# SEM002_2003_-_FanControl.net
KiCad netlist of a schematic drawn in EAGLE
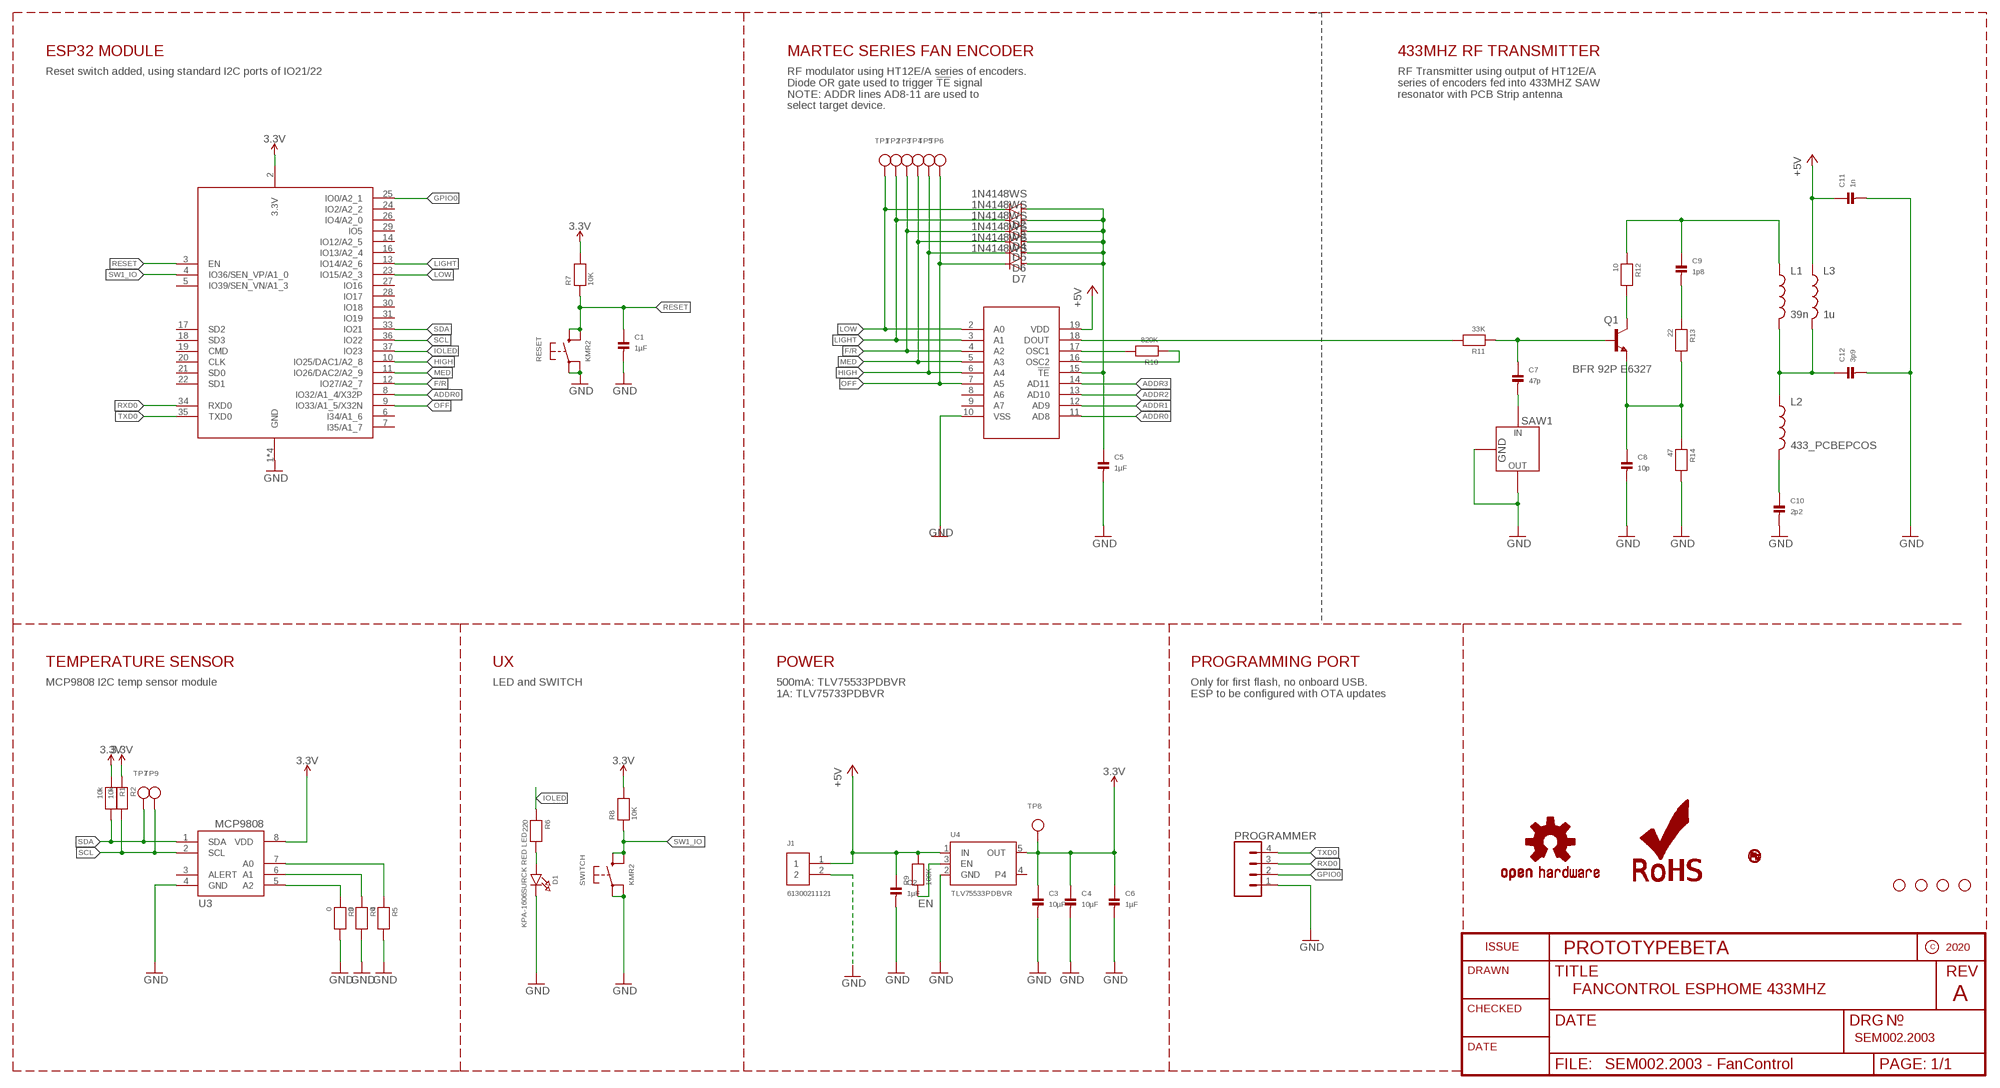
[diagram p0: schematic, sheet 1]

(export (version "E")
  (design (tool "Eeschema 10.0.6"))
  (components
    (comp (ref "C1")
      (value "1µF")
      (footprint "eagle-import:0603")
      (fields (field (name "MPN") "LMK107B7105KA-T"))
      (libsource (lib "eagle-import") (part "CAP_CERAMIC0603"))
    )
    (comp (ref "C2")
      (value "1µF")
      (footprint "eagle-import:0805_NOTHERMALS")
      (fields (field (name "MPN") "LMK107B7105KA-T"))
      (libsource (lib "eagle-import") (part "CAP_CERAMIC0805-NOTHERMALS"))
    )
    (comp (ref "C3")
      (value "10µF")
      (footprint "eagle-import:0603")
      (fields (field (name "MPN") "0805YD106MAT4A"))
      (libsource (lib "eagle-import") (part "CAP_CERAMIC0603"))
    )
    (comp (ref "C4")
      (value "10µF")
      (footprint "eagle-import:0805_NOTHERMALS")
      (fields (field (name "MPN") "0805YD106MAT4A"))
      (libsource (lib "eagle-import") (part "CAP_CERAMIC0805-NOTHERMALS"))
    )
    (comp (ref "C5")
      (value "1µF")
      (footprint "eagle-import:0603-MINI")
      (fields (field (name "MPN") "LMK107B7105KA-T"))
      (libsource (lib "eagle-import") (part "CAP_CERAMIC0603MINI"))
    )
    (comp (ref "C6")
      (value "1µF")
      (footprint "eagle-import:0603")
      (fields (field (name "MPN") "LMK107B7105KA-T"))
      (libsource (lib "eagle-import") (part "CAP_CERAMIC0603"))
    )
    (comp (ref "C7")
      (value "47p")
      (footprint "eagle-import:0603-MINI")
      (fields (field (name "MPN") "0603N470F500CT"))
      (libsource (lib "eagle-import") (part "CAP_CERAMIC0603MINI"))
    )
    (comp (ref "C8")
      (value "10p")
      (footprint "eagle-import:0603-MINI")
      (fields (field (name "MPN") "0603N100F500CT"))
      (libsource (lib "eagle-import") (part "CAP_CERAMIC0603MINI"))
    )
    (comp (ref "C9")
      (value "1p8")
      (footprint "eagle-import:0603-MINI")
      (fields (field (name "MPN") "0603N1R8B101CT"))
      (libsource (lib "eagle-import") (part "CAP_CERAMIC0603MINI"))
    )
    (comp (ref "C10")
      (value "2p2")
      (footprint "eagle-import:0603-MINI")
      (fields (field (name "MPN") "0603N2R2B101CT"))
      (libsource (lib "eagle-import") (part "CAP_CERAMIC0603MINI"))
    )
    (comp (ref "C11")
      (value "1n")
      (footprint "eagle-import:0603-MINI")
      (fields (field (name "MPN") "0603N102F500CT"))
      (libsource (lib "eagle-import") (part "CAP_CERAMIC0603MINI"))
    )
    (comp (ref "C12")
      (value "3p9")
      (footprint "eagle-import:0603-MINI")
      (fields (field (name "MPN") "0603N3R9B101CT"))
      (libsource (lib "eagle-import") (part "CAP_CERAMIC0603MINI"))
    )
    (comp (ref "D1")
      (value "KPA-1606SURCK RED LED")
      (footprint "eagle-import:CHIPLED_0603")
      (fields (field (name "MPN") "SML-H12U8TT86C"))
      (libsource (lib "eagle-import") (part "LED0603"))
    )
    (comp (ref "D2")
      (value "1N4148WS")
      (footprint "eagle-import:SOD-323")
      (fields
        (field (name "DIGIKEY_PART_NUMBER") "1N4148WSFSTR-ND")
        (field (name "MANUFACTURER") "Diodes Incorporated")
        (field (name "CREATED_BY") "PCBLayout.com")
      )
      (libsource (lib "eagle-import") (part "1N4148WS"))
    )
    (comp (ref "D3")
      (value "1N4148WS")
      (footprint "eagle-import:SOD-323")
      (fields
        (field (name "DIGIKEY_PART_NUMBER") "1N4148WSFSTR-ND")
        (field (name "MANUFACTURER") "Diodes Incorporated")
        (field (name "CREATED_BY") "PCBLayout.com")
      )
      (libsource (lib "eagle-import") (part "1N4148WS"))
    )
    (comp (ref "D4")
      (value "1N4148WS")
      (footprint "eagle-import:SOD-323")
      (fields
        (field (name "DIGIKEY_PART_NUMBER") "1N4148WSFSTR-ND")
        (field (name "MANUFACTURER") "Diodes Incorporated")
        (field (name "CREATED_BY") "PCBLayout.com")
      )
      (libsource (lib "eagle-import") (part "1N4148WS"))
    )
    (comp (ref "D5")
      (value "1N4148WS")
      (footprint "eagle-import:SOD-323")
      (fields
        (field (name "DIGIKEY_PART_NUMBER") "1N4148WSFSTR-ND")
        (field (name "MANUFACTURER") "Diodes Incorporated")
        (field (name "CREATED_BY") "PCBLayout.com")
      )
      (libsource (lib "eagle-import") (part "1N4148WS"))
    )
    (comp (ref "D6")
      (value "1N4148WS")
      (footprint "eagle-import:SOD-323")
      (fields
        (field (name "DIGIKEY_PART_NUMBER") "1N4148WSFSTR-ND")
        (field (name "MANUFACTURER") "Diodes Incorporated")
        (field (name "CREATED_BY") "PCBLayout.com")
      )
      (libsource (lib "eagle-import") (part "1N4148WS"))
    )
    (comp (ref "D7")
      (value "1N4148WS")
      (footprint "eagle-import:SOD-323")
      (fields
        (field (name "DIGIKEY_PART_NUMBER") "1N4148WSFSTR-ND")
        (field (name "MANUFACTURER") "Diodes Incorporated")
        (field (name "CREATED_BY") "PCBLayout.com")
      )
      (libsource (lib "eagle-import") (part "1N4148WS"))
    )
    (comp (ref "H1")
      (value "STAND-OFF")
      (footprint "eagle-import:STAND-OFF")
      (libsource (lib "eagle-import") (part "STAND-OFF"))
    )
    (comp (ref "H2")
      (value "STAND-OFF")
      (footprint "eagle-import:STAND-OFF")
      (libsource (lib "eagle-import") (part "STAND-OFF"))
    )
    (comp (ref "H3")
      (value "STAND-OFF")
      (footprint "eagle-import:STAND-OFF")
      (libsource (lib "eagle-import") (part "STAND-OFF"))
    )
    (comp (ref "H4")
      (value "STAND-OFF")
      (footprint "eagle-import:STAND-OFF")
      (libsource (lib "eagle-import") (part "STAND-OFF"))
    )
    (comp (ref "J1")
      (value "61300211121")
      (footprint "eagle-import:61300211121")
      (fields
        (field (name "DIGI_KEY_PART_NUMBER") "732-5315-ND")
        (field (name "MANUFACTURER") "Wurth Electronics Inc.")
        (field (name "CREATED_BY") "PCBLayout.com")
      )
      (libsource (lib "eagle-import") (part "61300211121"))
    )
    (comp (ref "L1")
      (value "39n")
      (footprint "eagle-import:L0603")
      (fields (field (name "MPN") "CI160808-39NJ"))
      (libsource (lib "eagle-import") (part "INDUCTOR"))
    )
    (comp (ref "L2")
      (value "433_PCBEPCOS")
      (footprint "eagle-import:433MHZ-SAW")
      (libsource (lib "eagle-import") (part "433_PCBEPCOS"))
    )
    (comp (ref "L3")
      (value "1u")
      (footprint "eagle-import:L0603")
      (fields (field (name "MPN") "AIML-0603-1R0K-T"))
      (libsource (lib "eagle-import") (part "INDUCTOR"))
    )
    (comp (ref "LOGO1")
      (value "OSHW-LOGOM")
      (footprint "eagle-import:OSHW-LOGO-M")
      (libsource (lib "eagle-import") (part "OSHW-LOGOM"))
    )
    (comp (ref "LOGO2")
      (value "ROHS_LOGO")
      (footprint "eagle-import:ROHS_LOGO_0.18_IN")
      (libsource (lib "eagle-import") (part "ROHS_LOGO"))
    )
    (comp (ref "LOGO3")
      (value "NO_PB_LOGO")
      (footprint "eagle-import:NO_PB_LOGO_0.120")
      (libsource (lib "eagle-import") (part "NO_PB_LOGO"))
    )
    (comp (ref "PROGRAMMER")
      (value "CONN_04")
      (footprint "eagle-import:1X04")
      (libsource (lib "eagle-import") (part "CONN_04"))
    )
    (comp (ref "Q1")
      (value "BFR 92P E6327")
      (footprint "eagle-import:SOT23")
      (fields
        (field (name "DIGIKEY_PART_NUMBER") "MMBT3904FSCT-ND")
        (field (name "MANUFACTURER") "ON Semiconductor")
        (field (name "MPN") "MMBT3904")
        (field (name "MPN_1") "BFR92PE6327")
        (field (name "CREATED_BY") "PCBLayout.com")
      )
      (libsource (lib "eagle-import") (part "MMBT3904"))
    )
    (comp (ref "R1")
      (value "10k")
      (footprint "eagle-import:0603")
      (fields (field (name "MPN") "APC0603B10K0N"))
      (libsource (lib "eagle-import") (part "RESISTOR0603"))
    )
    (comp (ref "R2")
      (value "10k")
      (footprint "eagle-import:0603")
      (fields (field (name "MPN") "APC0603B10K0N"))
      (libsource (lib "eagle-import") (part "RESISTOR0603"))
    )
    (comp (ref "R3")
      (value "0")
      (footprint "eagle-import:0603")
      (fields (field (name "MPN") "CRCW06030000Z0EAC"))
      (libsource (lib "eagle-import") (part "RESISTOR0603"))
    )
    (comp (ref "R4")
      (value "0")
      (footprint "eagle-import:0603")
      (fields (field (name "MPN") "CRCW06030000Z0EAC"))
      (libsource (lib "eagle-import") (part "RESISTOR0603"))
    )
    (comp (ref "R5")
      (value "0")
      (footprint "eagle-import:0603")
      (fields (field (name "MPN") "CRCW06030000Z0EAC"))
      (libsource (lib "eagle-import") (part "RESISTOR0603"))
    )
    (comp (ref "R6")
      (value "220")
      (footprint "eagle-import:0603")
      (fields (field (name "MPN") "CRCW0603220RFKEAC"))
      (libsource (lib "eagle-import") (part "RESISTOR0603"))
    )
    (comp (ref "R7")
      (value "10K")
      (footprint "eagle-import:0603")
      (fields (field (name "MPN") "APC0603B10K0N"))
      (libsource (lib "eagle-import") (part "RESISTOR0603"))
    )
    (comp (ref "R8")
      (value "10K")
      (footprint "eagle-import:0603")
      (fields (field (name "MPN") "APC0603B10K0N"))
      (libsource (lib "eagle-import") (part "RESISTOR0603"))
    )
    (comp (ref "R9")
      (value "100K")
      (footprint "eagle-import:0603-MINI")
      (fields (field (name "MPN") "CRCW0603100KFKEAC"))
      (libsource (lib "eagle-import") (part "RESISTOR0603MINI"))
    )
    (comp (ref "R10")
      (value "820K")
      (footprint "eagle-import:0603")
      (fields (field (name "MPN") "ERJ-3EKF8203V"))
      (libsource (lib "eagle-import") (part "RESISTOR0603"))
    )
    (comp (ref "R11")
      (value "33K")
      (footprint "eagle-import:0603-MINI")
      (fields (field (name "MPN") "CRCW06033K30FKEAC"))
      (libsource (lib "eagle-import") (part "RESISTOR0603MINI"))
    )
    (comp (ref "R12")
      (value "10")
      (footprint "eagle-import:0603-MINI")
      (fields (field (name "MPN") "RR0816Q-100-D"))
      (libsource (lib "eagle-import") (part "RESISTOR0603MINI"))
    )
    (comp (ref "R13")
      (value "22")
      (footprint "eagle-import:0603-MINI")
      (fields (field (name "MPN") "RR0816Q-220-D"))
      (libsource (lib "eagle-import") (part "RESISTOR0603MINI"))
    )
    (comp (ref "R14")
      (value "47")
      (footprint "eagle-import:0603-MINI")
      (fields (field (name "MPN") "ERA-3AED470V"))
      (libsource (lib "eagle-import") (part "RESISTOR0603MINI"))
    )
    (comp (ref "RESET")
      (value "KMR2")
      (footprint "eagle-import:BTN_KMR2_4.6X2.8")
      (fields (field (name "MPN") "KMR221GLFS"))
      (libsource (lib "eagle-import") (part "SWITCH_TACT_SMT4.6X2.8"))
    )
    (comp (ref "SAW1")
      (value "R727QCC8C")
      (footprint "eagle-import:QCC8C")
      (fields (field (name "MPN") "B39431B3730H110"))
      (libsource (lib "eagle-import") (part "R727QCC8C"))
    )
    (comp (ref "SWITCH")
      (value "KMR2")
      (footprint "eagle-import:BTN_KMR2_4.6X2.8")
      (fields (field (name "MPN") "KMR221GLFS"))
      (libsource (lib "eagle-import") (part "SWITCH_TACT_SMT4.6X2.8"))
    )
    (comp (ref "TP1")
      (value "TESTPOINTROUND1MM")
      (footprint "eagle-import:TESTPOINT_ROUND_1MM")
      (fields (field (name "MPN") "DNL"))
      (libsource (lib "eagle-import") (part "TESTPOINTROUND1MM"))
    )
    (comp (ref "TP2")
      (value "TESTPOINTROUND1MM")
      (footprint "eagle-import:TESTPOINT_ROUND_1MM")
      (fields (field (name "MPN") "DNL"))
      (libsource (lib "eagle-import") (part "TESTPOINTROUND1MM"))
    )
    (comp (ref "TP3")
      (value "TESTPOINTROUND1MM")
      (footprint "eagle-import:TESTPOINT_ROUND_1MM")
      (fields (field (name "MPN") "DNL"))
      (libsource (lib "eagle-import") (part "TESTPOINTROUND1MM"))
    )
    (comp (ref "TP4")
      (value "TESTPOINTROUND1MM")
      (footprint "eagle-import:TESTPOINT_ROUND_1MM")
      (fields (field (name "MPN") "DNL"))
      (libsource (lib "eagle-import") (part "TESTPOINTROUND1MM"))
    )
    (comp (ref "TP5")
      (value "TESTPOINTROUND1MM")
      (footprint "eagle-import:TESTPOINT_ROUND_1MM")
      (fields (field (name "MPN") "DNL"))
      (libsource (lib "eagle-import") (part "TESTPOINTROUND1MM"))
    )
    (comp (ref "TP6")
      (value "TESTPOINTROUND1MM")
      (footprint "eagle-import:TESTPOINT_ROUND_1MM")
      (fields (field (name "MPN") "DNL"))
      (libsource (lib "eagle-import") (part "TESTPOINTROUND1MM"))
    )
    (comp (ref "TP7")
      (value "TESTPOINTROUND1MM")
      (footprint "eagle-import:TESTPOINT_ROUND_1MM")
      (fields (field (name "MPN") "DNL"))
      (libsource (lib "eagle-import") (part "TESTPOINTROUND1MM"))
    )
    (comp (ref "TP8")
      (value "TESTPOINTROUND1MM")
      (footprint "eagle-import:TESTPOINT_ROUND_1MM")
      (libsource (lib "eagle-import") (part "TESTPOINTROUND1MM"))
    )
    (comp (ref "TP9")
      (value "TESTPOINTROUND1MM")
      (footprint "eagle-import:TESTPOINT_ROUND_1MM")
      (fields (field (name "MPN") "DNL"))
      (libsource (lib "eagle-import") (part "TESTPOINTROUND1MM"))
    )
    (comp (ref "U1")
      (value "ESP32_WROOM32_SKINNY")
      (footprint "eagle-import:WROOM32_SKINNY")
      (fields (field (name "MPN") "ESP32-WROOM-32"))
      (libsource (lib "eagle-import") (part "ESP32_WROOM32_SKINNY"))
    )
    (comp (ref "U2")
      (value "HT12ESO20")
      (footprint "eagle-import:SO20_SOT163-1-R")
      (fields (field (name "MPN") "HT12E-20SOP"))
      (libsource (lib "eagle-import") (part "HT12ESO20"))
    )
    (comp (ref "U3")
      (value "MCP9808-E/MS")
      (footprint "eagle-import:MSOP8_0.65MM")
      (libsource (lib "eagle-import") (part "MCP9808-E/MS"))
    )
    (comp (ref "U4")
      (value "TLV75533PDBVR")
      (footprint "eagle-import:SOT23-5")
      (fields (field (name "CURRENT") "1A") (field (name "MPN") "TLV75733PDBVR"))
      (libsource (lib "eagle-import") (part "VREG_SOT23-5"))
    )
  )
  (nets
    (net (code "1") (name "+5V") (class "Default")
      (node (ref "C11") (pin "1") (pinfunction "P$1_1") (pintype "passive"))
      (node (ref "C2") (pin "1") (pinfunction "P$1_1") (pintype "passive"))
      (node (ref "J1") (pin "1") (pinfunction "1_1") (pintype "passive"))
      (node (ref "L3") (pin "1") (pinfunction "1_1") (pintype "passive"))
      (node (ref "R9") (pin "2") (pinfunction "2_2") (pintype "passive"))
      (node (ref "U2") (pin "19") (pinfunction "VDD_19") (pintype "bidirectional"))
      (node (ref "U4") (pin "1") (pinfunction "IN_1") (pintype "power_in"))
    )
    (net (code "2") (name "/EN") (class "Default")
      (node (ref "R9") (pin "1") (pinfunction "1_1") (pintype "passive"))
      (node (ref "U4") (pin "3") (pinfunction "EN_3") (pintype "input"))
    )
    (net (code "3") (name "3.3V") (class "Default")
      (node (ref "C3") (pin "1") (pinfunction "P$1_1") (pintype "passive"))
      (node (ref "C4") (pin "1") (pinfunction "P$1_1") (pintype "passive"))
      (node (ref "C6") (pin "1") (pinfunction "P$1_1") (pintype "passive"))
      (node (ref "R1") (pin "1") (pinfunction "1_1") (pintype "passive"))
      (node (ref "R2") (pin "1") (pinfunction "1_1") (pintype "passive"))
      (node (ref "R7") (pin "2") (pinfunction "2_2") (pintype "passive"))
      (node (ref "R8") (pin "2") (pinfunction "2_2") (pintype "passive"))
      (node (ref "TP8") (pin "P$1") (pinfunction "P$1_P$1") (pintype "bidirectional"))
      (node (ref "U1") (pin "2") (pinfunction "3.3V_2") (pintype "passive"))
      (node (ref "U3") (pin "8") (pinfunction "VDD_8") (pintype "power_in"))
      (node (ref "U4") (pin "5") (pinfunction "OUT_5") (pintype "power_in"))
    )
    (net (code "4") (name "ADDR0") (class "Default")
      (node (ref "U1") (pin "8") (pinfunction "IO32/A1_4/X32P_8") (pintype "bidirectional"))
      (node (ref "U2") (pin "11") (pinfunction "AD8_11") (pintype "bidirectional"))
    )
    (net (code "5") (name "ADDR1") (class "Default")
      (node (ref "U2") (pin "12") (pinfunction "AD9_12") (pintype "bidirectional"))
    )
    (net (code "6") (name "ADDR2") (class "Default")
      (node (ref "U2") (pin "13") (pinfunction "AD10_13") (pintype "bidirectional"))
    )
    (net (code "7") (name "ADDR3") (class "Default")
      (node (ref "U2") (pin "14") (pinfunction "AD11_14") (pintype "bidirectional"))
    )
    (net (code "8") (name "F{slash}R") (class "Default")
      (node (ref "D4") (pin "C") (pinfunction "C_C") (pintype "passive"))
      (node (ref "TP3") (pin "P$1") (pinfunction "P$1_P$1") (pintype "bidirectional"))
      (node (ref "U1") (pin "12") (pinfunction "IO27/A2_7_12") (pintype "bidirectional"))
      (node (ref "U2") (pin "4") (pinfunction "A2_4") (pintype "bidirectional"))
    )
    (net (code "9") (name "GND") (class "Default")
      (node (ref "C1") (pin "2") (pinfunction "P$2_2") (pintype "passive"))
      (node (ref "C10") (pin "2") (pinfunction "P$2_2") (pintype "passive"))
      (node (ref "C11") (pin "2") (pinfunction "P$2_2") (pintype "passive"))
      (node (ref "C12") (pin "2") (pinfunction "P$2_2") (pintype "passive"))
      (node (ref "C2") (pin "2") (pinfunction "P$2_2") (pintype "passive"))
      (node (ref "C3") (pin "2") (pinfunction "P$2_2") (pintype "passive"))
      (node (ref "C4") (pin "2") (pinfunction "P$2_2") (pintype "passive"))
      (node (ref "C5") (pin "2") (pinfunction "P$2_2") (pintype "passive"))
      (node (ref "C6") (pin "2") (pinfunction "P$2_2") (pintype "passive"))
      (node (ref "C8") (pin "2") (pinfunction "P$2_2") (pintype "passive"))
      (node (ref "D1") (pin "C") (pinfunction "C_C") (pintype "passive"))
      (node (ref "J1") (pin "2") (pinfunction "2_2") (pintype "passive"))
      (node (ref "PROGRAMMER") (pin "1") (pinfunction "1_1") (pintype "passive"))
      (node (ref "R14") (pin "2") (pinfunction "2_2") (pintype "passive"))
      (node (ref "R3") (pin "2") (pinfunction "2_2") (pintype "passive"))
      (node (ref "R4") (pin "2") (pinfunction "2_2") (pintype "passive"))
      (node (ref "R5") (pin "2") (pinfunction "2_2") (pintype "passive"))
      (node (ref "RESET") (pin "A") (pinfunction "P_A") (pintype "passive"))
      (node (ref "RESET") (pin "A'") (pinfunction "P1_A'") (pintype "passive"))
      (node (ref "SAW1") (pin "P$1") (pinfunction "P$3_P$1") (pintype "bidirectional"))
      (node (ref "SAW1") (pin "P$3") (pinfunction "P$3_P$3") (pintype "bidirectional"))
      (node (ref "SAW1") (pin "P$4") (pinfunction "P$3_P$4") (pintype "bidirectional"))
      (node (ref "SAW1") (pin "P$5") (pinfunction "P$2_P$5") (pintype "bidirectional"))
      (node (ref "SAW1") (pin "P$6") (pinfunction "P$3_P$6") (pintype "bidirectional"))
      (node (ref "SWITCH") (pin "A") (pinfunction "P_A") (pintype "passive"))
      (node (ref "SWITCH") (pin "A'") (pinfunction "P1_A'") (pintype "passive"))
      (node (ref "U1") (pin "1") (pinfunction "GND_1") (pintype "passive"))
      (node (ref "U1") (pin "15") (pinfunction "GND_15") (pintype "passive"))
      (node (ref "U1") (pin "38") (pinfunction "GND_38") (pintype "passive"))
      (node (ref "U1") (pin "P$1") (pinfunction "GND_P$1") (pintype "passive"))
      (node (ref "U2") (pin "10") (pinfunction "VSS_10") (pintype "bidirectional"))
      (node (ref "U3") (pin "4") (pinfunction "GND_4") (pintype "power_in"))
      (node (ref "U4") (pin "2") (pinfunction "GND_2") (pintype "power_in"))
    )
    (net (code "10") (name "GPIO0") (class "Default")
      (node (ref "PROGRAMMER") (pin "2") (pinfunction "2_2") (pintype "passive"))
      (node (ref "U1") (pin "25") (pinfunction "IO0/A2_1_25") (pintype "bidirectional"))
    )
    (net (code "11") (name "HIGH") (class "Default")
      (node (ref "D6") (pin "C") (pinfunction "C_C") (pintype "passive"))
      (node (ref "TP5") (pin "P$1") (pinfunction "P$1_P$1") (pintype "bidirectional"))
      (node (ref "U1") (pin "10") (pinfunction "IO25/DAC1/A2_8_10") (pintype "bidirectional"))
      (node (ref "U2") (pin "6") (pinfunction "A4_6") (pintype "bidirectional"))
    )
    (net (code "12") (name "IOLED") (class "Default")
      (node (ref "R6") (pin "1") (pinfunction "1_1") (pintype "passive"))
      (node (ref "U1") (pin "37") (pinfunction "IO23_37") (pintype "bidirectional"))
    )
    (net (code "13") (name "LIGHT") (class "Default")
      (node (ref "D3") (pin "C") (pinfunction "C_C") (pintype "passive"))
      (node (ref "TP2") (pin "P$1") (pinfunction "P$1_P$1") (pintype "bidirectional"))
      (node (ref "U1") (pin "13") (pinfunction "IO14/A2_6_13") (pintype "bidirectional"))
      (node (ref "U2") (pin "3") (pinfunction "A1_3") (pintype "bidirectional"))
    )
    (net (code "14") (name "LOW") (class "Default")
      (node (ref "D2") (pin "C") (pinfunction "C_C") (pintype "passive"))
      (node (ref "TP1") (pin "P$1") (pinfunction "P$1_P$1") (pintype "bidirectional"))
      (node (ref "U1") (pin "23") (pinfunction "IO15/A2_3_23") (pintype "bidirectional"))
      (node (ref "U2") (pin "2") (pinfunction "A0_2") (pintype "bidirectional"))
    )
    (net (code "15") (name "MED") (class "Default")
      (node (ref "D5") (pin "C") (pinfunction "C_C") (pintype "passive"))
      (node (ref "TP4") (pin "P$1") (pinfunction "P$1_P$1") (pintype "bidirectional"))
      (node (ref "U1") (pin "11") (pinfunction "IO26/DAC2/A2_9_11") (pintype "bidirectional"))
      (node (ref "U2") (pin "5") (pinfunction "A3_5") (pintype "bidirectional"))
    )
    (net (code "16") (name "Net-(C5-P$1)") (class "Default")
      (node (ref "C5") (pin "1") (pinfunction "P$1_1") (pintype "passive"))
      (node (ref "D2") (pin "A") (pinfunction "A_A") (pintype "passive"))
      (node (ref "D3") (pin "A") (pinfunction "A_A") (pintype "passive"))
      (node (ref "D4") (pin "A") (pinfunction "A_A") (pintype "passive"))
      (node (ref "D5") (pin "A") (pinfunction "A_A") (pintype "passive"))
      (node (ref "D6") (pin "A") (pinfunction "A_A") (pintype "passive"))
      (node (ref "D7") (pin "A") (pinfunction "A_A") (pintype "passive"))
      (node (ref "U2") (pin "15") (pinfunction "~{TE}_15") (pintype "bidirectional"))
    )
    (net (code "17") (name "Net-(C7-P$1)") (class "Default")
      (node (ref "C7") (pin "1") (pinfunction "P$1_1") (pintype "passive"))
      (node (ref "Q1") (pin "1") (pinfunction "B_1") (pintype "passive"))
      (node (ref "R11") (pin "1") (pinfunction "1_1") (pintype "passive"))
    )
    (net (code "18") (name "Net-(C7-P$2)") (class "Default")
      (node (ref "C7") (pin "2") (pinfunction "P$2_2") (pintype "passive"))
      (node (ref "SAW1") (pin "P$2") (pinfunction "P$1_P$2") (pintype "bidirectional"))
    )
    (net (code "19") (name "Net-(C8-P$1)") (class "Default")
      (node (ref "C8") (pin "1") (pinfunction "P$1_1") (pintype "passive"))
      (node (ref "Q1") (pin "2") (pinfunction "E_2") (pintype "passive"))
      (node (ref "R13") (pin "2") (pinfunction "2_2") (pintype "passive"))
      (node (ref "R14") (pin "1") (pinfunction "1_1") (pintype "passive"))
    )
    (net (code "20") (name "Net-(C9-P$1)") (class "Default")
      (node (ref "C9") (pin "1") (pinfunction "P$1_1") (pintype "passive"))
      (node (ref "L1") (pin "1") (pinfunction "1_1") (pintype "passive"))
      (node (ref "R12") (pin "1") (pinfunction "1_1") (pintype "passive"))
    )
    (net (code "21") (name "Net-(C9-P$2)") (class "Default")
      (node (ref "C9") (pin "2") (pinfunction "P$2_2") (pintype "passive"))
      (node (ref "R13") (pin "1") (pinfunction "1_1") (pintype "passive"))
    )
    (net (code "22") (name "Net-(C10-P$1)") (class "Default")
      (node (ref "C10") (pin "1") (pinfunction "P$1_1") (pintype "passive"))
      (node (ref "L2") (pin "P$2") (pinfunction "2_P$2") (pintype "passive"))
    )
    (net (code "23") (name "Net-(C12-P$1)") (class "Default")
      (node (ref "C12") (pin "1") (pinfunction "P$1_1") (pintype "passive"))
      (node (ref "L1") (pin "2") (pinfunction "2_2") (pintype "passive"))
      (node (ref "L2") (pin "P$1") (pinfunction "1_P$1") (pintype "passive"))
      (node (ref "L3") (pin "2") (pinfunction "2_2") (pintype "passive"))
    )
    (net (code "24") (name "Net-(D1-PadA)") (class "Default")
      (node (ref "D1") (pin "A") (pinfunction "A_A") (pintype "passive"))
      (node (ref "R6") (pin "2") (pinfunction "2_2") (pintype "passive"))
    )
    (net (code "25") (name "Net-(Q1-C)") (class "Default")
      (node (ref "Q1") (pin "3") (pinfunction "C_3") (pintype "passive"))
      (node (ref "R12") (pin "2") (pinfunction "2_2") (pintype "passive"))
    )
    (net (code "26") (name "Net-(U2-DOUT)") (class "Default")
      (node (ref "R11") (pin "2") (pinfunction "2_2") (pintype "passive"))
      (node (ref "U2") (pin "18") (pinfunction "DOUT_18") (pintype "bidirectional"))
    )
    (net (code "27") (name "Net-(U2-OSC1)") (class "Default")
      (node (ref "R10") (pin "2") (pinfunction "2_2") (pintype "passive"))
      (node (ref "U2") (pin "17") (pinfunction "OSC1_17") (pintype "bidirectional"))
    )
    (net (code "28") (name "Net-(U2-OSC2)") (class "Default")
      (node (ref "R10") (pin "1") (pinfunction "1_1") (pintype "passive"))
      (node (ref "U2") (pin "16") (pinfunction "OSC2_16") (pintype "bidirectional"))
    )
    (net (code "29") (name "Net-(U3-A0)") (class "Default")
      (node (ref "R5") (pin "1") (pinfunction "1_1") (pintype "passive"))
      (node (ref "U3") (pin "7") (pinfunction "A0_7") (pintype "input"))
    )
    (net (code "30") (name "Net-(U3-A1)") (class "Default")
      (node (ref "R4") (pin "1") (pinfunction "1_1") (pintype "passive"))
      (node (ref "U3") (pin "6") (pinfunction "A1_6") (pintype "input"))
    )
    (net (code "31") (name "Net-(U3-A2)") (class "Default")
      (node (ref "R3") (pin "1") (pinfunction "1_1") (pintype "passive"))
      (node (ref "U3") (pin "5") (pinfunction "A2_5") (pintype "input"))
    )
    (net (code "32") (name "OFF") (class "Default")
      (node (ref "D7") (pin "C") (pinfunction "C_C") (pintype "passive"))
      (node (ref "TP6") (pin "P$1") (pinfunction "P$1_P$1") (pintype "bidirectional"))
      (node (ref "U1") (pin "9") (pinfunction "IO33/A1_5/X32N_9") (pintype "bidirectional"))
      (node (ref "U2") (pin "7") (pinfunction "A5_7") (pintype "bidirectional"))
    )
    (net (code "33") (name "RESET") (class "Default")
      (node (ref "C1") (pin "1") (pinfunction "P$1_1") (pintype "passive"))
      (node (ref "R7") (pin "1") (pinfunction "1_1") (pintype "passive"))
      (node (ref "RESET") (pin "B") (pinfunction "S_B") (pintype "passive"))
      (node (ref "RESET") (pin "B'") (pinfunction "S1_B'") (pintype "passive"))
      (node (ref "U1") (pin "3") (pinfunction "EN_3") (pintype "input"))
    )
    (net (code "34") (name "RXD0") (class "Default")
      (node (ref "PROGRAMMER") (pin "3") (pinfunction "3_3") (pintype "passive"))
      (node (ref "U1") (pin "34") (pinfunction "RXD0_34") (pintype "input"))
    )
    (net (code "35") (name "SCL") (class "Default")
      (node (ref "R2") (pin "2") (pinfunction "2_2") (pintype "passive"))
      (node (ref "TP9") (pin "P$1") (pinfunction "P$1_P$1") (pintype "bidirectional"))
      (node (ref "U1") (pin "36") (pinfunction "IO22_36") (pintype "bidirectional"))
      (node (ref "U3") (pin "2") (pinfunction "SCL_2") (pintype "bidirectional"))
    )
    (net (code "36") (name "SDA") (class "Default")
      (node (ref "R1") (pin "2") (pinfunction "2_2") (pintype "passive"))
      (node (ref "TP7") (pin "P$1") (pinfunction "P$1_P$1") (pintype "bidirectional"))
      (node (ref "U1") (pin "33") (pinfunction "IO21_33") (pintype "bidirectional"))
      (node (ref "U3") (pin "1") (pinfunction "SDA_1") (pintype "bidirectional"))
    )
    (net (code "37") (name "SW1_IO") (class "Default")
      (node (ref "R8") (pin "1") (pinfunction "1_1") (pintype "passive"))
      (node (ref "SWITCH") (pin "B") (pinfunction "S_B") (pintype "passive"))
      (node (ref "SWITCH") (pin "B'") (pinfunction "S1_B'") (pintype "passive"))
      (node (ref "U1") (pin "4") (pinfunction "IO36/SEN_VP/A1_0_4") (pintype "passive"))
    )
    (net (code "38") (name "TXD0") (class "Default")
      (node (ref "PROGRAMMER") (pin "4") (pinfunction "4_4") (pintype "passive"))
      (node (ref "U1") (pin "35") (pinfunction "TXD0_35") (pintype "output"))
    )
    (net (code "39") (name "unconnected-(U1-CLK-Pad20)") (class "Default")
      (node (ref "U1") (pin "20") (pinfunction "CLK_20") (pintype "bidirectional"))
    )
    (net (code "40") (name "unconnected-(U1-CMD-Pad19)") (class "Default")
      (node (ref "U1") (pin "19") (pinfunction "CMD_19") (pintype "bidirectional"))
    )
    (net (code "41") (name "unconnected-(U1-I34{slash}A1_6-Pad6)") (class "Default")
      (node (ref "U1") (pin "6") (pinfunction "I34/A1_6_6") (pintype "bidirectional"))
    )
    (net (code "42") (name "unconnected-(U1-I35{slash}A1_7-Pad7)") (class "Default")
      (node (ref "U1") (pin "7") (pinfunction "I35/A1_7_7") (pintype "bidirectional"))
    )
    (net (code "43") (name "unconnected-(U1-IO2{slash}A2_2-Pad24)") (class "Default")
      (node (ref "U1") (pin "24") (pinfunction "IO2/A2_2_24") (pintype "bidirectional"))
    )
    (net (code "44") (name "unconnected-(U1-IO4{slash}A2_0-Pad26)") (class "Default")
      (node (ref "U1") (pin "26") (pinfunction "IO4/A2_0_26") (pintype "bidirectional"))
    )
    (net (code "45") (name "unconnected-(U1-IO5-Pad29)") (class "Default")
      (node (ref "U1") (pin "29") (pinfunction "IO5_29") (pintype "bidirectional"))
    )
    (net (code "46") (name "unconnected-(U1-IO12{slash}A2_5-Pad14)") (class "Default")
      (node (ref "U1") (pin "14") (pinfunction "IO12/A2_5_14") (pintype "bidirectional"))
    )
    (net (code "47") (name "unconnected-(U1-IO13{slash}A2_4-Pad16)") (class "Default")
      (node (ref "U1") (pin "16") (pinfunction "IO13/A2_4_16") (pintype "bidirectional"))
    )
    (net (code "48") (name "unconnected-(U1-IO16-Pad27)") (class "Default")
      (node (ref "U1") (pin "27") (pinfunction "IO16_27") (pintype "bidirectional"))
    )
    (net (code "49") (name "unconnected-(U1-IO17-Pad28)") (class "Default")
      (node (ref "U1") (pin "28") (pinfunction "IO17_28") (pintype "bidirectional"))
    )
    (net (code "50") (name "unconnected-(U1-IO18-Pad30)") (class "Default")
      (node (ref "U1") (pin "30") (pinfunction "IO18_30") (pintype "bidirectional"))
    )
    (net (code "51") (name "unconnected-(U1-IO19-Pad31)") (class "Default")
      (node (ref "U1") (pin "31") (pinfunction "IO19_31") (pintype "bidirectional"))
    )
    (net (code "52") (name "unconnected-(U1-IO39{slash}SEN_VN{slash}A1_3-Pad5)") (class "Default")
      (node (ref "U1") (pin "5") (pinfunction "IO39/SEN_VN/A1_3_5") (pintype "passive"))
    )
    (net (code "53") (name "unconnected-(U1-SD0-Pad21)") (class "Default")
      (node (ref "U1") (pin "21") (pinfunction "SD0_21") (pintype "bidirectional"))
    )
    (net (code "54") (name "unconnected-(U1-SD1-Pad22)") (class "Default")
      (node (ref "U1") (pin "22") (pinfunction "SD1_22") (pintype "bidirectional"))
    )
    (net (code "55") (name "unconnected-(U1-SD2-Pad17)") (class "Default")
      (node (ref "U1") (pin "17") (pinfunction "SD2_17") (pintype "bidirectional"))
    )
    (net (code "56") (name "unconnected-(U1-SD3-Pad18)") (class "Default")
      (node (ref "U1") (pin "18") (pinfunction "SD3_18") (pintype "bidirectional"))
    )
    (net (code "57") (name "unconnected-(U2-A6-Pad8)") (class "Default")
      (node (ref "U2") (pin "8") (pinfunction "A6_8") (pintype "bidirectional"))
    )
    (net (code "58") (name "unconnected-(U2-A7-Pad9)") (class "Default")
      (node (ref "U2") (pin "9") (pinfunction "A7_9") (pintype "bidirectional"))
    )
    (net (code "59") (name "unconnected-(U3-ALERT-Pad3)") (class "Default")
      (node (ref "U3") (pin "3") (pinfunction "ALERT_3") (pintype "open_collector"))
    )
    (net (code "60") (name "unconnected-(U4-P4-Pad4)") (class "Default")
      (node (ref "U4") (pin "4") (pinfunction "P4_4") (pintype "bidirectional"))
    )
  )
)
